# CAPACITOR.net
KiCad netlist of a schematic drawn in Altium Designer
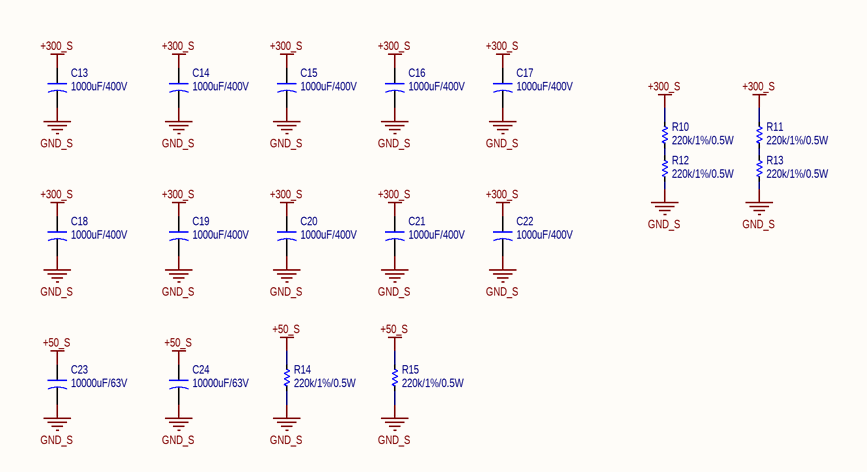
[diagram p0: CAPACITOR.SchDoc]

(export (version "E")
  (design (tool "Eeschema 10.0.6"))
  (components
    (comp (ref "C13")
      (value "1000uF/400V")
      (footprint "CA-ALU-35x50")
      (description "NO PN")
      (fields (field (name "PUBLISHER") "Altium Limited"))
      (libsource (lib "Library") (part "CN-ALU-DIP"))
    )
    (comp (ref "C14")
      (value "1000uF/400V")
      (footprint "CA-ALU-35x50")
      (description "NO PN")
      (fields (field (name "PUBLISHER") "Altium Limited"))
      (libsource (lib "Library") (part "CN-ALU-DIP"))
    )
    (comp (ref "C15")
      (value "1000uF/400V")
      (footprint "CA-ALU-35x50")
      (description "NO PN")
      (fields (field (name "PUBLISHER") "Altium Limited"))
      (libsource (lib "Library") (part "CN-ALU-DIP"))
    )
    (comp (ref "C16")
      (value "1000uF/400V")
      (footprint "CA-ALU-35x50")
      (description "NO PN")
      (fields (field (name "PUBLISHER") "Altium Limited"))
      (libsource (lib "Library") (part "CN-ALU-DIP"))
    )
    (comp (ref "C17")
      (value "1000uF/400V")
      (footprint "CA-ALU-35x50")
      (description "NO PN")
      (fields (field (name "PUBLISHER") "Altium Limited"))
      (libsource (lib "Library") (part "CN-ALU-DIP"))
    )
    (comp (ref "C18")
      (value "1000uF/400V")
      (footprint "CA-ALU-35x50")
      (description "NO PN")
      (fields (field (name "PUBLISHER") "Altium Limited"))
      (libsource (lib "Library") (part "CN-ALU-DIP"))
    )
    (comp (ref "C19")
      (value "1000uF/400V")
      (footprint "CA-ALU-35x50")
      (description "NO PN")
      (fields (field (name "PUBLISHER") "Altium Limited"))
      (libsource (lib "Library") (part "CN-ALU-DIP"))
    )
    (comp (ref "C20")
      (value "1000uF/400V")
      (footprint "CA-ALU-35x50")
      (description "NO PN")
      (fields (field (name "PUBLISHER") "Altium Limited"))
      (libsource (lib "Library") (part "CN-ALU-DIP"))
    )
    (comp (ref "C21")
      (value "1000uF/400V")
      (footprint "CA-ALU-35x50")
      (description "NO PN")
      (fields (field (name "PUBLISHER") "Altium Limited"))
      (libsource (lib "Library") (part "CN-ALU-DIP"))
    )
    (comp (ref "C22")
      (value "1000uF/400V")
      (footprint "CA-ALU-35x50")
      (description "NO PN")
      (fields (field (name "PUBLISHER") "Altium Limited"))
      (libsource (lib "Library") (part "CN-ALU-DIP"))
    )
    (comp (ref "C23")
      (value "10000uF/63V")
      (footprint "CA-ALU-35x50")
      (description "NO PN")
      (fields (field (name "PUBLISHER") "Altium Limited"))
      (libsource (lib "Library") (part "CN-ALU-DIP"))
    )
    (comp (ref "C24")
      (value "10000uF/63V")
      (footprint "CA-ALU-35x50")
      (description "NO PN")
      (fields (field (name "PUBLISHER") "Altium Limited"))
      (libsource (lib "Library") (part "CN-ALU-DIP"))
    )
    (comp (ref "R10")
      (value "220k/1%/0.5W")
      (footprint "RES-SMD-2010")
      (description "RES SMD 220K OHM 1% 1/2W 2010")
      (fields
        (field (name "MANUFACTURER") "Generic Components")
        (field (name "PUBLISHER") "Altium Hobart Technology Centre")
      )
      (libsource (lib "Library") (part "Res-SMD"))
    )
    (comp (ref "R11")
      (value "220k/1%/0.5W")
      (footprint "RES-SMD-2010")
      (description "RES SMD 220K OHM 1% 1/2W 2010")
      (fields
        (field (name "MANUFACTURER") "Generic Components")
        (field (name "PUBLISHER") "Altium Hobart Technology Centre")
      )
      (libsource (lib "Library") (part "Res-SMD"))
    )
    (comp (ref "R12")
      (value "220k/1%/0.5W")
      (footprint "RES-SMD-2010")
      (description "RES SMD 220K OHM 1% 1/2W 2010")
      (fields
        (field (name "MANUFACTURER") "Generic Components")
        (field (name "PUBLISHER") "Altium Hobart Technology Centre")
      )
      (libsource (lib "Library") (part "Res-SMD"))
    )
    (comp (ref "R13")
      (value "220k/1%/0.5W")
      (footprint "RES-SMD-2010")
      (description "RES SMD 220K OHM 1% 1/2W 2010")
      (fields
        (field (name "MANUFACTURER") "Generic Components")
        (field (name "PUBLISHER") "Altium Hobart Technology Centre")
      )
      (libsource (lib "Library") (part "Res-SMD"))
    )
    (comp (ref "R14")
      (value "220k/1%/0.5W")
      (footprint "RES-SMD-2010")
      (description "RES SMD 220K OHM 1% 1/2W 2010")
      (fields
        (field (name "MANUFACTURER") "Generic Components")
        (field (name "PUBLISHER") "Altium Hobart Technology Centre")
      )
      (libsource (lib "Library") (part "Res-SMD"))
    )
    (comp (ref "R15")
      (value "220k/1%/0.5W")
      (footprint "RES-SMD-2010")
      (description "RES SMD 220K OHM 1% 1/2W 2010")
      (fields
        (field (name "MANUFACTURER") "Generic Components")
        (field (name "PUBLISHER") "Altium Hobart Technology Centre")
      )
      (libsource (lib "Library") (part "Res-SMD"))
    )
  )
  (nets
    (net (code "1") (name "+50_S") (class "Default")
      (node (ref "C23") (pin "1") (pinfunction "1_1") (pintype "passive"))
      (node (ref "C24") (pin "1") (pinfunction "1_1") (pintype "passive"))
      (node (ref "R14") (pin "1") (pinfunction "1_1") (pintype "passive"))
      (node (ref "R15") (pin "1") (pinfunction "1_1") (pintype "passive"))
    )
    (net (code "2") (name "+300_S") (class "Default")
      (node (ref "C13") (pin "1") (pinfunction "1_1") (pintype "passive"))
      (node (ref "C14") (pin "1") (pinfunction "1_1") (pintype "passive"))
      (node (ref "C15") (pin "1") (pinfunction "1_1") (pintype "passive"))
      (node (ref "C16") (pin "1") (pinfunction "1_1") (pintype "passive"))
      (node (ref "C17") (pin "1") (pinfunction "1_1") (pintype "passive"))
      (node (ref "C18") (pin "1") (pinfunction "1_1") (pintype "passive"))
      (node (ref "C19") (pin "1") (pinfunction "1_1") (pintype "passive"))
      (node (ref "C20") (pin "1") (pinfunction "1_1") (pintype "passive"))
      (node (ref "C21") (pin "1") (pinfunction "1_1") (pintype "passive"))
      (node (ref "C22") (pin "1") (pinfunction "1_1") (pintype "passive"))
      (node (ref "R10") (pin "1") (pinfunction "1_1") (pintype "passive"))
      (node (ref "R11") (pin "1") (pinfunction "1_1") (pintype "passive"))
    )
    (net (code "3") (name "GND_S") (class "Default")
      (node (ref "C13") (pin "2") (pinfunction "2_2") (pintype "passive"))
      (node (ref "C14") (pin "2") (pinfunction "2_2") (pintype "passive"))
      (node (ref "C15") (pin "2") (pinfunction "2_2") (pintype "passive"))
      (node (ref "C16") (pin "2") (pinfunction "2_2") (pintype "passive"))
      (node (ref "C17") (pin "2") (pinfunction "2_2") (pintype "passive"))
      (node (ref "C18") (pin "2") (pinfunction "2_2") (pintype "passive"))
      (node (ref "C19") (pin "2") (pinfunction "2_2") (pintype "passive"))
      (node (ref "C20") (pin "2") (pinfunction "2_2") (pintype "passive"))
      (node (ref "C21") (pin "2") (pinfunction "2_2") (pintype "passive"))
      (node (ref "C22") (pin "2") (pinfunction "2_2") (pintype "passive"))
      (node (ref "C23") (pin "2") (pinfunction "2_2") (pintype "passive"))
      (node (ref "C24") (pin "2") (pinfunction "2_2") (pintype "passive"))
      (node (ref "R12") (pin "2") (pinfunction "2_2") (pintype "passive"))
      (node (ref "R13") (pin "2") (pinfunction "2_2") (pintype "passive"))
      (node (ref "R14") (pin "2") (pinfunction "2_2") (pintype "passive"))
      (node (ref "R15") (pin "2") (pinfunction "2_2") (pintype "passive"))
    )
    (net (code "4") (name "Net-(R10-Pad2)") (class "Default")
      (node (ref "R10") (pin "2") (pinfunction "2_2") (pintype "passive"))
      (node (ref "R12") (pin "1") (pinfunction "1_1") (pintype "passive"))
    )
    (net (code "5") (name "Net-(R11-Pad2)") (class "Default")
      (node (ref "R11") (pin "2") (pinfunction "2_2") (pintype "passive"))
      (node (ref "R13") (pin "1") (pinfunction "1_1") (pintype "passive"))
    )
  )
)
